# Uni-2_3.net
KiCad netlist of a schematic drawn in EAGLE
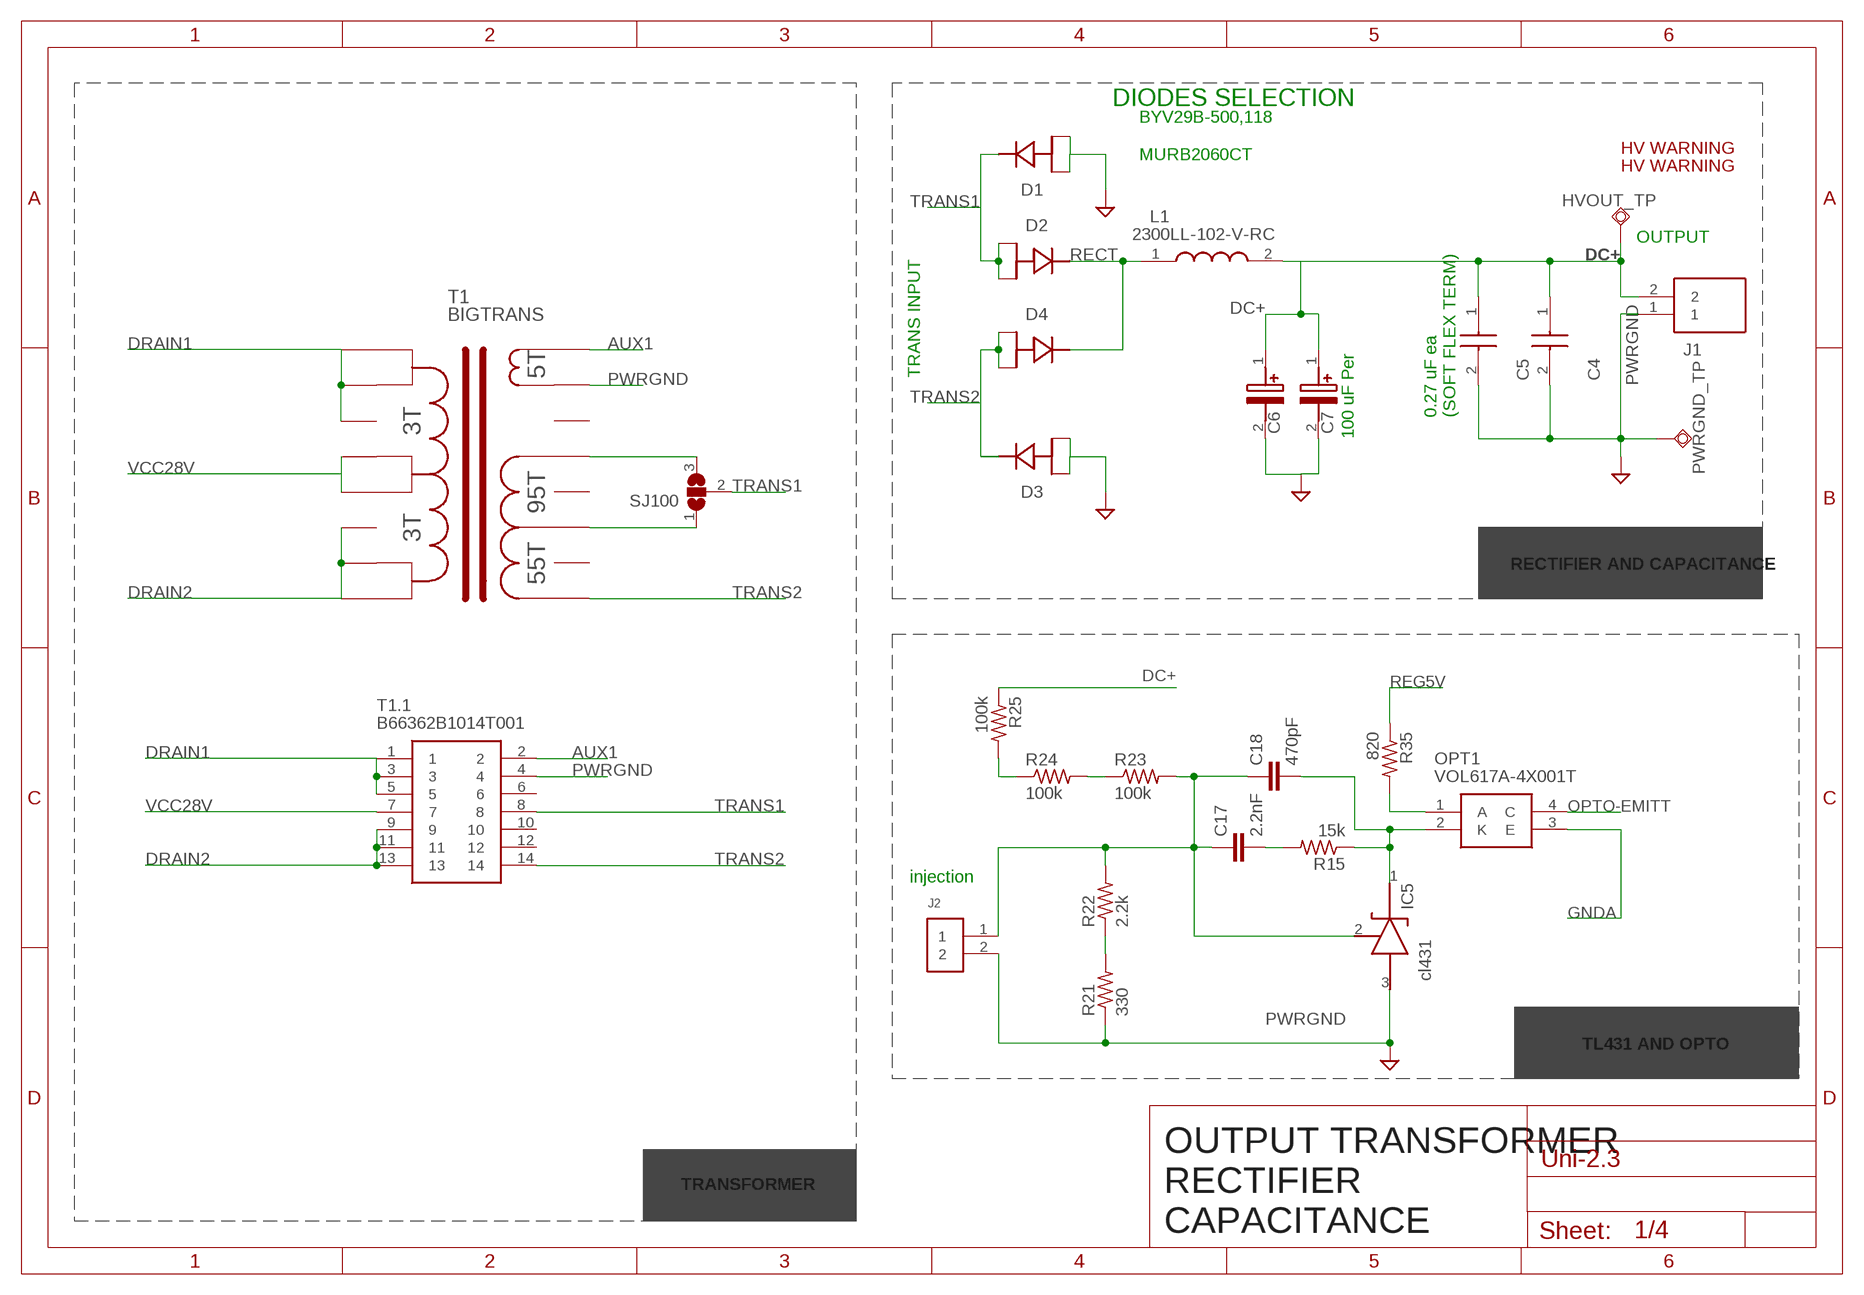
[diagram p0: schematic, sheet 1]
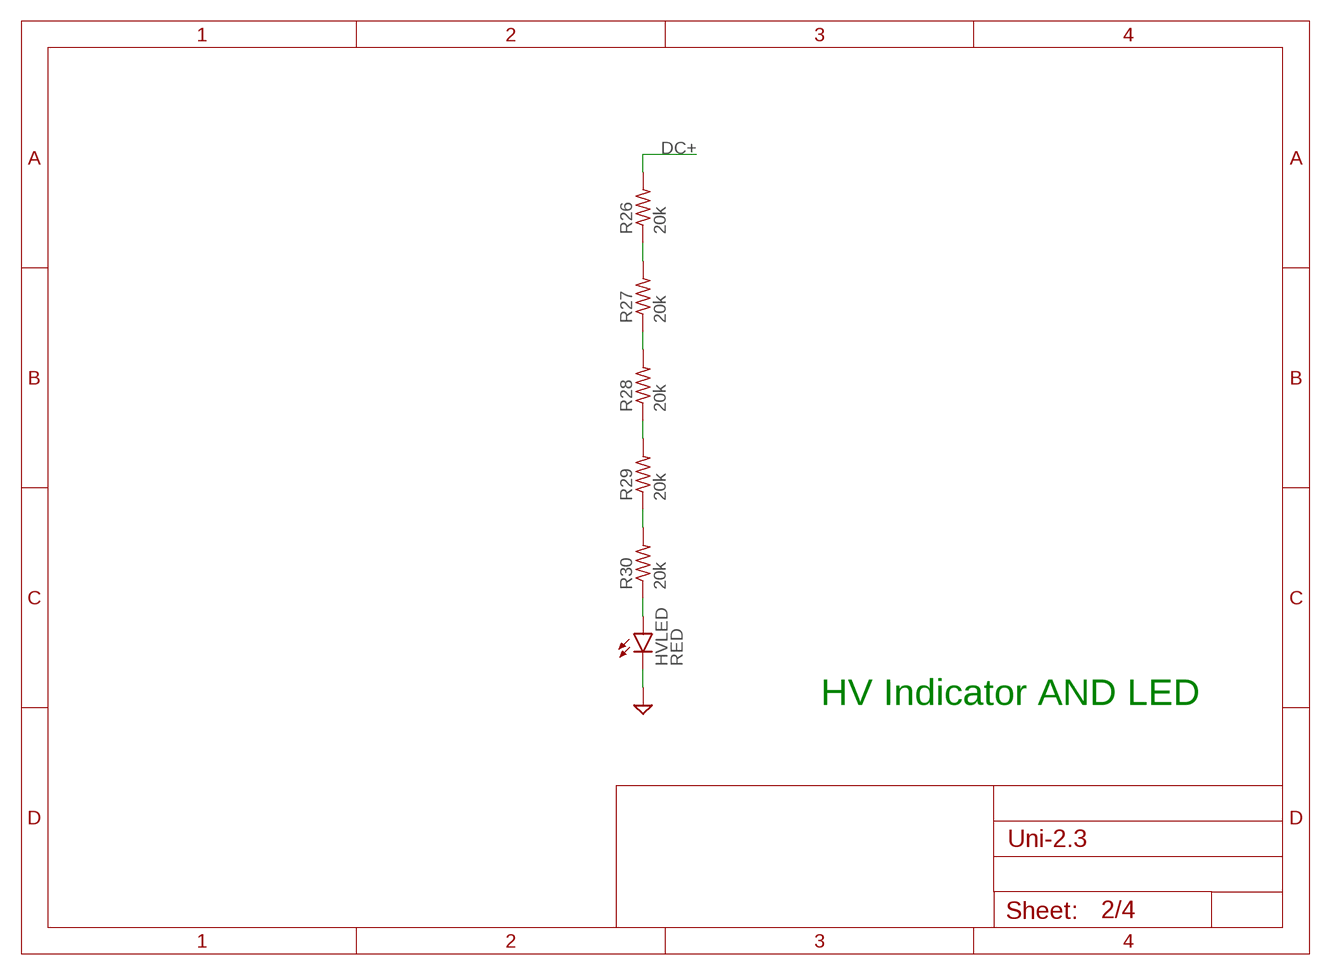
[diagram p1: schematic, sheet 2]
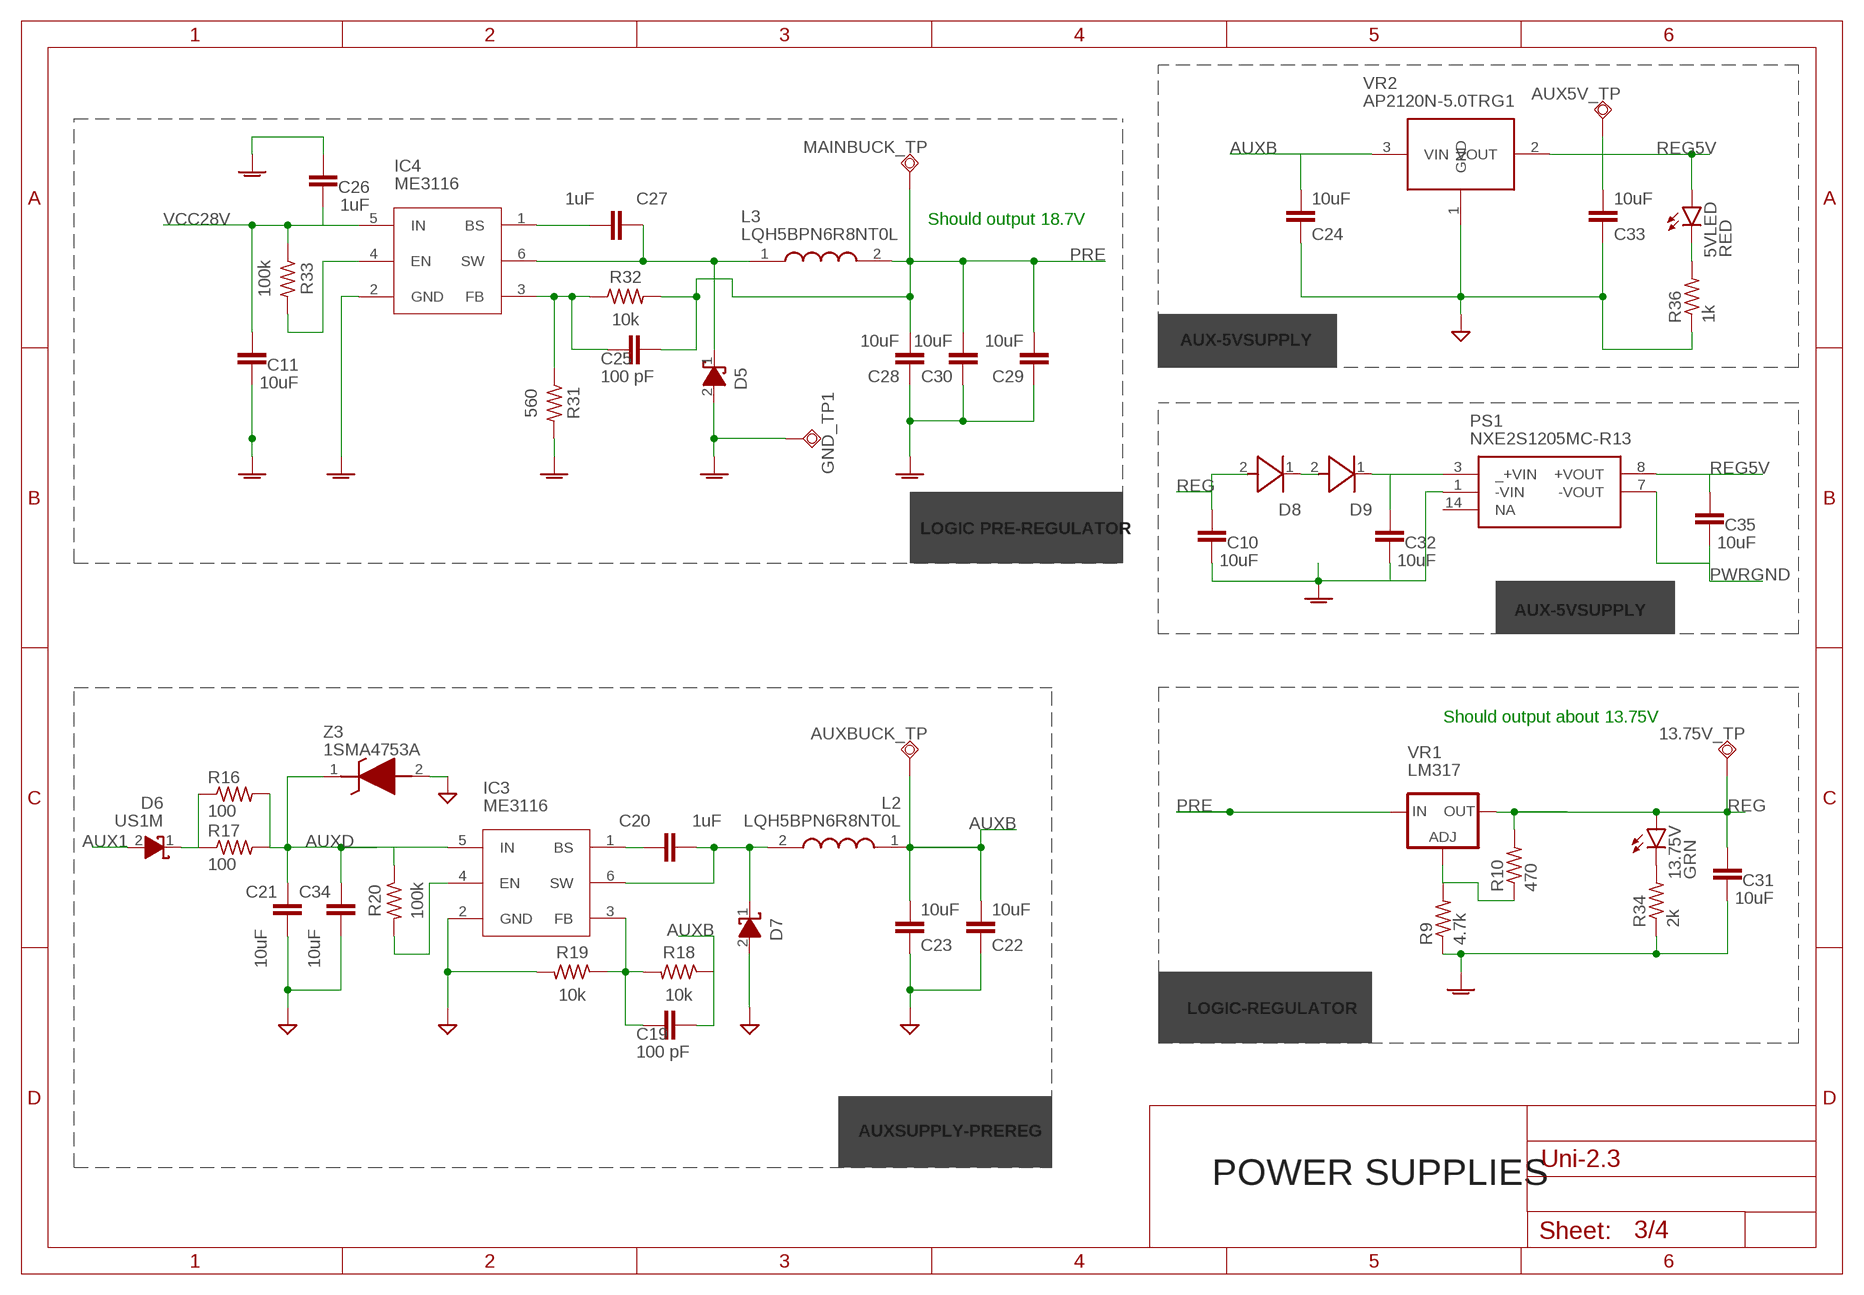
[diagram p2: schematic, sheet 3]
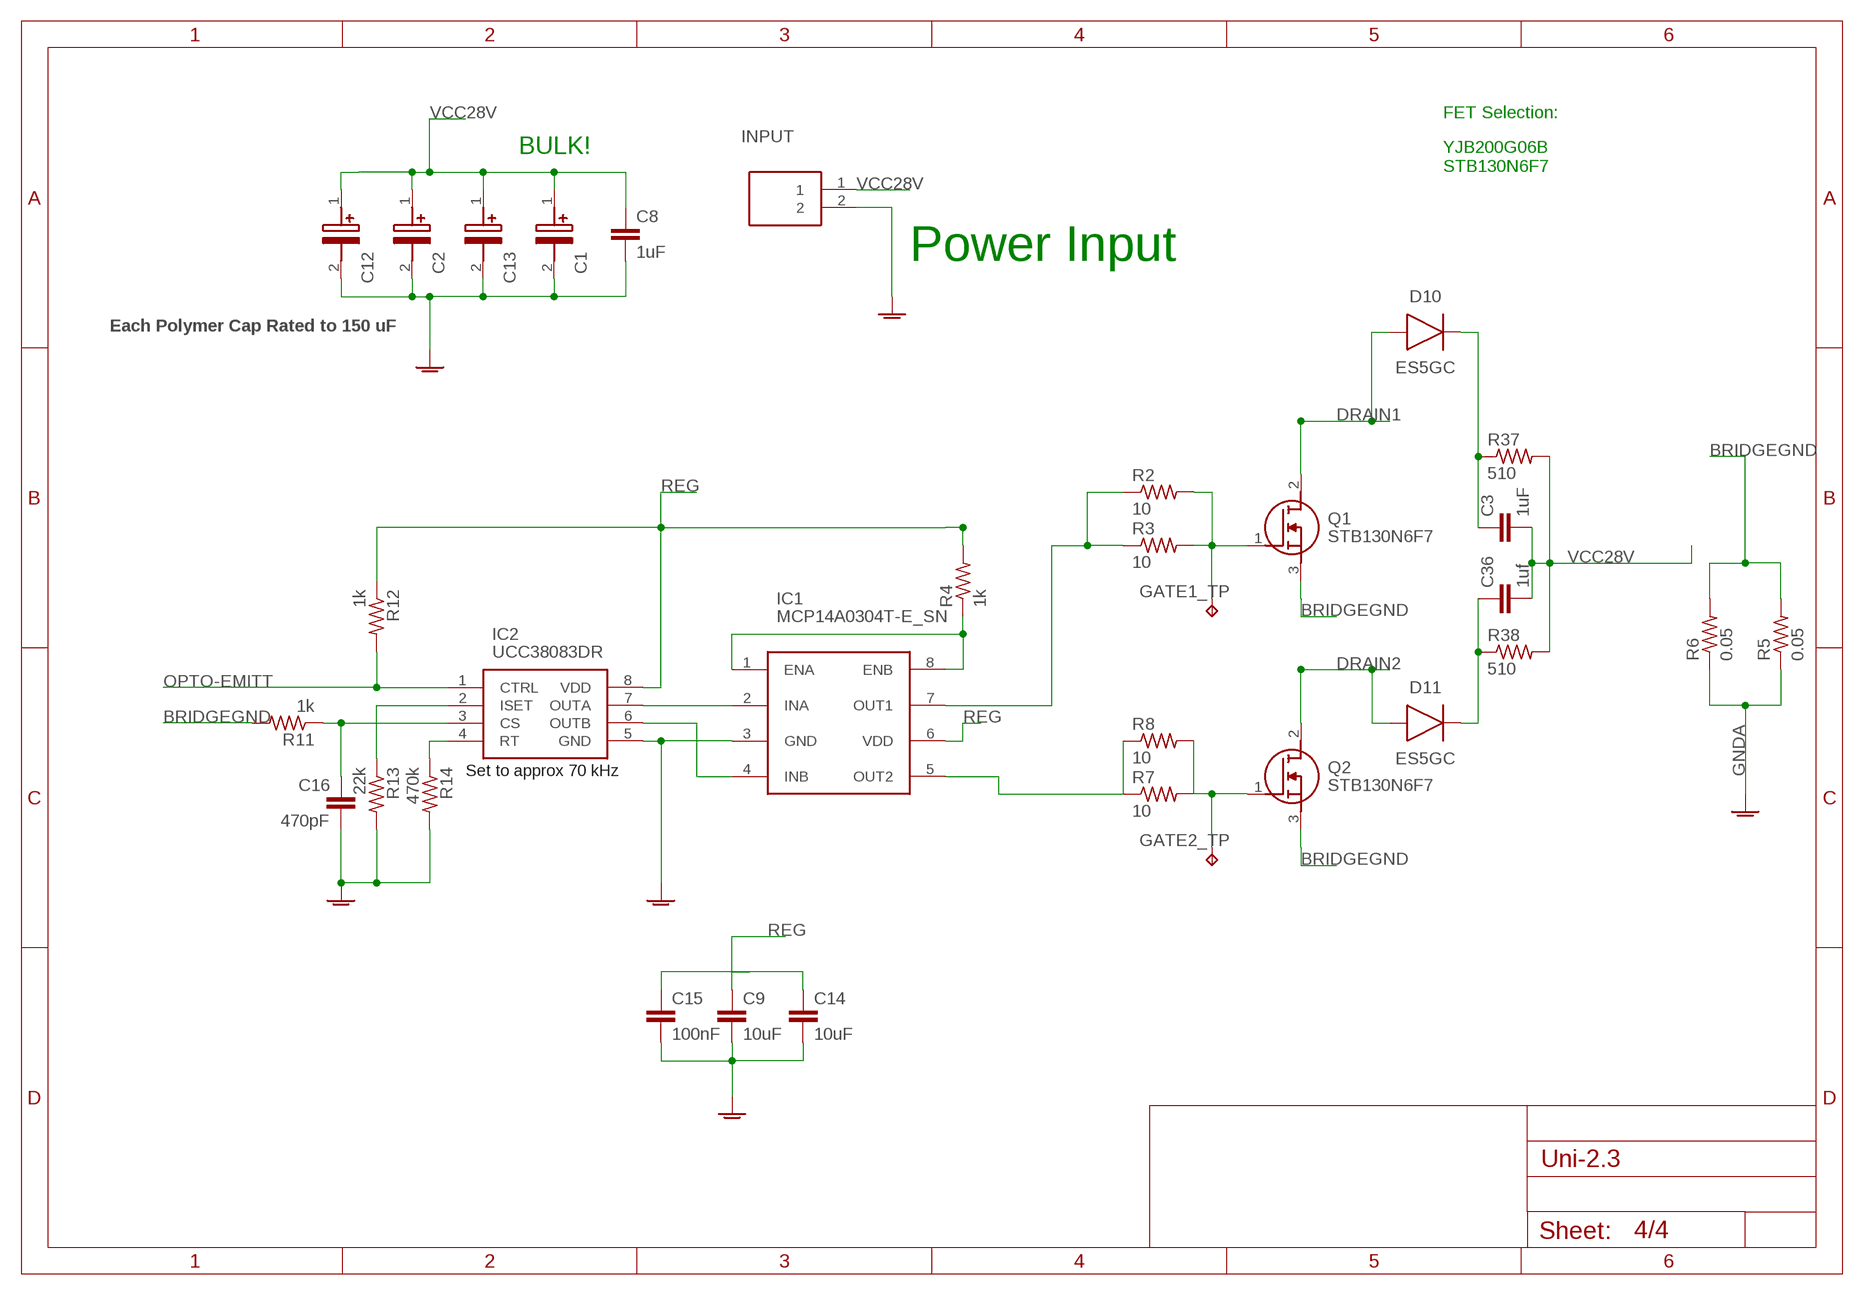
[diagram p3: schematic, sheet 4]

(export (version "E")
  (design (tool "Eeschema 10.0.6"))
  (components
    (comp (ref "HVLED")
      (value "RED")
      (footprint "eagle-import:CHIPLED_0805")
      (libsource (lib "eagle-import") (part "LEDCHIPLED_0805"))
    )
    (comp (ref "R26")
      (value "20k")
      (footprint "eagle-import:R1206")
      (libsource (lib "eagle-import") (part "R-US_R1206"))
    )
    (comp (ref "R27")
      (value "20k")
      (footprint "eagle-import:R1206")
      (libsource (lib "eagle-import") (part "R-US_R1206"))
    )
    (comp (ref "R28")
      (value "20k")
      (footprint "eagle-import:R1206")
      (libsource (lib "eagle-import") (part "R-US_R1206"))
    )
    (comp (ref "R29")
      (value "20k")
      (footprint "eagle-import:R1206")
      (libsource (lib "eagle-import") (part "R-US_R1206"))
    )
    (comp (ref "R30")
      (value "20k")
      (footprint "eagle-import:R1206")
      (libsource (lib "eagle-import") (part "R-US_R1206"))
    )
    (comp (ref "C1")
      (value "OVK151M1VTR-10131")
      (footprint "eagle-import:16SVF1000M")
      (libsource (lib "eagle-import") (part "OVK151M1VTR-10131"))
    )
    (comp (ref "C2")
      (value "OVK151M1VTR-10131")
      (footprint "eagle-import:16SVF1000M")
      (libsource (lib "eagle-import") (part "OVK151M1VTR-10131"))
    )
    (comp (ref "C3")
      (value "1uF")
      (footprint "eagle-import:C1206K")
      (libsource (lib "eagle-import") (part "rcl_334_C-EUC1206K"))
    )
    (comp (ref "C8")
      (value "1uF")
      (footprint "eagle-import:C0805K")
      (fields (field (name "LCSC_PART") "C440198"))
      (libsource (lib "eagle-import") (part "rcl_334_C-EUC0805K"))
    )
    (comp (ref "C9")
      (value "10uF")
      (footprint "eagle-import:C0603K")
      (fields (field (name "LCSC_PART") "C440198"))
      (libsource (lib "eagle-import") (part "rcl_334_C-EUC0603K"))
    )
    (comp (ref "C12")
      (value "OVK151M1VTR-10131")
      (footprint "eagle-import:16SVF1000M")
      (libsource (lib "eagle-import") (part "OVK151M1VTR-10131"))
    )
    (comp (ref "C13")
      (value "OVK151M1VTR-10131")
      (footprint "eagle-import:16SVF1000M")
      (libsource (lib "eagle-import") (part "OVK151M1VTR-10131"))
    )
    (comp (ref "C14")
      (value "10uF")
      (footprint "eagle-import:C0603K")
      (fields (field (name "LCSC_PART") "C440198"))
      (libsource (lib "eagle-import") (part "rcl_334_C-EUC0603K"))
    )
    (comp (ref "C15")
      (value "100nF")
      (footprint "eagle-import:C0603K")
      (fields (field (name "LCSC_PART") "C440198"))
      (libsource (lib "eagle-import") (part "rcl_334_C-EUC0603K"))
    )
    (comp (ref "C16")
      (value "470pF")
      (footprint "eagle-import:C0603K")
      (fields (field (name "LCSC_PART") "C1620"))
      (libsource (lib "eagle-import") (part "rcl_334_C-EUC0603K"))
    )
    (comp (ref "C36")
      (value "1uf")
      (footprint "eagle-import:C1206K")
      (libsource (lib "eagle-import") (part "rcl_334_C-EUC1206K"))
    )
    (comp (ref "D10")
      (value "ES5GC")
      (footprint "eagle-import:DIOM5226X290N")
      (fields (field (name "LCSC_PART") "C128705"))
      (libsource (lib "eagle-import") (part "DIODEDO-214AC(SMA)"))
    )
    (comp (ref "D11")
      (value "ES5GC")
      (footprint "eagle-import:DIOM5226X290N")
      (libsource (lib "eagle-import") (part "DIODEDO-214AC(SMA)"))
    )
    (comp (ref "GATE1_TP")
      (value "TPTP13R")
      (footprint "eagle-import:TP13R")
      (libsource (lib "eagle-import") (part "TPTP13R"))
    )
    (comp (ref "GATE2_TP")
      (value "TPTP13R")
      (footprint "eagle-import:TP13R")
      (libsource (lib "eagle-import") (part "TPTP13R"))
    )
    (comp (ref "IC1")
      (value "MCP14A0304T-E_SN")
      (footprint "eagle-import:SOIC127P600X175-8N")
      (fields
        (field (name "MANUFACTURER_PART_NUMBER") "MCP14A0304T-E/SN")
        (field (name "MOUSER_PART_NUMBER") "579-MCP14A0304T-E/SN")
      )
      (libsource (lib "eagle-import") (part "MCP14A0304T-E_SN"))
    )
    (comp (ref "IC2")
      (value "UCC38083DR")
      (footprint "eagle-import:SOIC127P600X175-8N")
      (fields (field (name "MOUSER_PART_NUMBER") "595-UCC38083DR"))
      (libsource (lib "eagle-import") (part "UCC38083DR"))
    )
    (comp (ref "INPUT")
      (value "TB005-762-02BE")
      (footprint "eagle-import:TB00576202BE")
      (fields (field (name "MOUSER_PART_NUMBER") "490-TB005-762-02BE"))
      (libsource (lib "eagle-import") (part "TB005-762-02BE"))
    )
    (comp (ref "Q1")
      (value "STB130N6F7")
      (footprint "eagle-import:D2PAK")
      (libsource (lib "eagle-import") (part "STB130N6F7"))
    )
    (comp (ref "Q2")
      (value "STB130N6F7")
      (footprint "eagle-import:D2PAK")
      (libsource (lib "eagle-import") (part "STB130N6F7"))
    )
    (comp (ref "R2")
      (value "10")
      (footprint "eagle-import:R0805")
      (libsource (lib "eagle-import") (part "R-US_R0805"))
    )
    (comp (ref "R3")
      (value "10")
      (footprint "eagle-import:R0805")
      (libsource (lib "eagle-import") (part "R-US_R0805"))
    )
    (comp (ref "R4")
      (value "1k")
      (footprint "eagle-import:R0402")
      (libsource (lib "eagle-import") (part "R-US_R0402"))
    )
    (comp (ref "R5")
      (value "0.05")
      (footprint "eagle-import:R2512")
      (libsource (lib "eagle-import") (part "R-US_R2512"))
    )
    (comp (ref "R6")
      (value "0.05")
      (footprint "eagle-import:R2512")
      (libsource (lib "eagle-import") (part "R-US_R2512"))
    )
    (comp (ref "R7")
      (value "10")
      (footprint "eagle-import:R0805")
      (libsource (lib "eagle-import") (part "R-US_R0805"))
    )
    (comp (ref "R8")
      (value "10")
      (footprint "eagle-import:R0805")
      (libsource (lib "eagle-import") (part "R-US_R0805"))
    )
    (comp (ref "R11")
      (value "1k")
      (footprint "eagle-import:R0603")
      (fields (field (name "LCSC_PART") "C21190"))
      (libsource (lib "eagle-import") (part "R-US_R0603"))
    )
    (comp (ref "R12")
      (value "1k")
      (footprint "eagle-import:R0603")
      (fields (field (name "LCSC_PART") "C22975"))
      (libsource (lib "eagle-import") (part "R-US_R0603"))
    )
    (comp (ref "R13")
      (value "22k")
      (footprint "eagle-import:R0603")
      (fields (field (name "LCSC_PART") "C31850"))
      (libsource (lib "eagle-import") (part "R-US_R0603"))
    )
    (comp (ref "R14")
      (value "470k")
      (footprint "eagle-import:R0603")
      (fields (field (name "LCSC_PART") "C25811"))
      (libsource (lib "eagle-import") (part "R-US_R0603"))
    )
    (comp (ref "R37")
      (value "510")
      (footprint "eagle-import:R2512")
      (libsource (lib "eagle-import") (part "R-US_R2512"))
    )
    (comp (ref "R38")
      (value "510")
      (footprint "eagle-import:R2512")
      (libsource (lib "eagle-import") (part "R-US_R2512"))
    )
    (comp (ref "5VLED")
      (value "RED")
      (footprint "eagle-import:CHIPLED_0805")
      (fields (field (name "LCSC_PART") "C72043"))
      (libsource (lib "eagle-import") (part "LEDCHIPLED_0805"))
    )
    (comp (ref "13.75V")
      (value "GRN")
      (footprint "eagle-import:CHIPLED_0805")
      (fields (field (name "LCSC_PART") "C72043"))
      (libsource (lib "eagle-import") (part "LEDCHIPLED_0805"))
    )
    (comp (ref "13.75V_TP")
      (value "TPSQPAD1-17")
      (footprint "eagle-import:P1-17")
      (libsource (lib "eagle-import") (part "TPSQPAD1-17"))
    )
    (comp (ref "AUX5V_TP")
      (value "TPSQPAD1-17")
      (footprint "eagle-import:P1-17")
      (libsource (lib "eagle-import") (part "TPSQPAD1-17"))
    )
    (comp (ref "AUXBUCK_TP")
      (value "TPSQPAD1-17")
      (footprint "eagle-import:P1-17")
      (libsource (lib "eagle-import") (part "TPSQPAD1-17"))
    )
    (comp (ref "C10")
      (value "10uF")
      (footprint "eagle-import:C0805K")
      (fields (field (name "LCSC_PART") "C440198"))
      (libsource (lib "eagle-import") (part "C-EUC0805K"))
    )
    (comp (ref "C11")
      (value "10uF")
      (footprint "eagle-import:C0805K")
      (fields (field (name "LCSC_PART") "C440198"))
      (libsource (lib "eagle-import") (part "C-EUC0805K"))
    )
    (comp (ref "C19")
      (value "100 pF")
      (footprint "eagle-import:C0402K")
      (fields (field (name "LCSC_PART") "C1546"))
      (libsource (lib "eagle-import") (part "rcl_334_C-EUC0402K"))
    )
    (comp (ref "C20")
      (value "1uF")
      (footprint "eagle-import:C0603K")
      (fields (field (name "LCSC_PART") "C14663"))
      (libsource (lib "eagle-import") (part "rcl_334_C-EUC0603K"))
    )
    (comp (ref "C21")
      (value "10uF")
      (footprint "eagle-import:C0805K")
      (libsource (lib "eagle-import") (part "rcl_334_C-EUC0805K"))
    )
    (comp (ref "C22")
      (value "10uF")
      (footprint "eagle-import:C0402")
      (fields (field (name "LCSC_PART") "C440198"))
      (libsource (lib "eagle-import") (part "rcl_334_C-EUC0402"))
    )
    (comp (ref "C23")
      (value "10uF")
      (footprint "eagle-import:C0603K")
      (fields (field (name "LCSC_PART") "C440198"))
      (libsource (lib "eagle-import") (part "rcl_334_C-EUC0603K"))
    )
    (comp (ref "C24")
      (value "10uF")
      (footprint "eagle-import:C0603K")
      (fields (field (name "LCSC_PART") "C440198"))
      (libsource (lib "eagle-import") (part "rcl_334_C-EUC0603K"))
    )
    (comp (ref "C25")
      (value "100 pF")
      (footprint "eagle-import:C0402K")
      (fields (field (name "LCSC_PART") "C1546"))
      (libsource (lib "eagle-import") (part "rcl_334_C-EUC0402K"))
    )
    (comp (ref "C26")
      (value "1uF")
      (footprint "eagle-import:C0603K")
      (fields (field (name "LCSC_PART") "C440198"))
      (libsource (lib "eagle-import") (part "rcl_334_C-EUC0603K"))
    )
    (comp (ref "C27")
      (value "1uF")
      (footprint "eagle-import:C0603K")
      (fields (field (name "LCSC_PART") "C14663"))
      (libsource (lib "eagle-import") (part "rcl_334_C-EUC0603K"))
    )
    (comp (ref "C28")
      (value "10uF")
      (footprint "eagle-import:C0805K")
      (fields (field (name "LCSC_PART") "C440198"))
      (libsource (lib "eagle-import") (part "C-EUC0805K"))
    )
    (comp (ref "C29")
      (value "10uF")
      (footprint "eagle-import:C0805K")
      (fields (field (name "LCSC_PART") "C440198"))
      (libsource (lib "eagle-import") (part "C-EUC0805K"))
    )
    (comp (ref "C30")
      (value "10uF")
      (footprint "eagle-import:C0805K")
      (fields (field (name "LCSC_PART") "C440198"))
      (libsource (lib "eagle-import") (part "C-EUC0805K"))
    )
    (comp (ref "C31")
      (value "10uF")
      (footprint "eagle-import:C0805K")
      (fields (field (name "LCSC_PART") "C440198"))
      (libsource (lib "eagle-import") (part "C-EUC0805K"))
    )
    (comp (ref "C32")
      (value "10uF")
      (footprint "eagle-import:C0603K")
      (fields (field (name "LCSC_PART") "C440198"))
      (libsource (lib "eagle-import") (part "rcl_334_C-EUC0603K"))
    )
    (comp (ref "C33")
      (value "10uF")
      (footprint "eagle-import:C0603K")
      (libsource (lib "eagle-import") (part "rcl_334_C-EUC0603K"))
    )
    (comp (ref "C34")
      (value "10uF")
      (footprint "eagle-import:C0805K")
      (libsource (lib "eagle-import") (part "rcl_334_C-EUC0805K"))
    )
    (comp (ref "C35")
      (value "10uF")
      (footprint "eagle-import:C0603K")
      (fields (field (name "LCSC_PART") "C440198"))
      (libsource (lib "eagle-import") (part "rcl_334_C-EUC0603K"))
    )
    (comp (ref "D5")
      (value "SCHOTTKY")
      (footprint "eagle-import:DIOM5127X229N")
      (fields
        (field (name "MANUFACTURER_PART_NUMBER") "SS16HE3_B/H")
        (field (name "MOUSER_PART_NUMBER") "78-SS16HE3_B/H")
        (field (name "LCSC_PART") "C22452")
      )
      (libsource (lib "eagle-import") (part "SCHOTTKY"))
    )
    (comp (ref "D6")
      (value "US1M")
      (footprint "eagle-import:DIOM5127X229N")
      (fields
        (field (name "MANUFACTURER_PART_NUMBER") "SS16HE3_B/H")
        (field (name "MOUSER_PART_NUMBER") "78-SS16HE3_B/H")
      )
      (libsource (lib "eagle-import") (part "SCHOTTKY"))
    )
    (comp (ref "D7")
      (value "SCHOTTKY")
      (footprint "eagle-import:DIOM5127X229N")
      (fields
        (field (name "MANUFACTURER_PART_NUMBER") "SS16HE3_B/H")
        (field (name "MOUSER_PART_NUMBER") "78-SS16HE3_B/H")
        (field (name "LCSC_PART") "C22452")
      )
      (libsource (lib "eagle-import") (part "SCHOTTKY"))
    )
    (comp (ref "D8")
      (value "SM4007PL")
      (footprint "eagle-import:SOD3716X145N")
      (fields
        (field (name "MANUFACTURER_PART_NUMBER") "1N4148W-7-F")
        (field (name "MOUSER_PART_NUMBER") "621-1N4148W-F")
        (field (name "LCSC_PART") "C64898")
      )
      (libsource (lib "eagle-import") (part "1N4148W-7-F"))
    )
    (comp (ref "D9")
      (value "SM4007PL")
      (footprint "eagle-import:SOD3716X145N")
      (fields
        (field (name "MANUFACTURER_PART_NUMBER") "1N4148W-7-F")
        (field (name "MOUSER_PART_NUMBER") "621-1N4148W-F")
        (field (name "LCSC_PART") "C64898")
      )
      (libsource (lib "eagle-import") (part "1N4148W-7-F"))
    )
    (comp (ref "GND_TP1")
      (value "TPSQPAD1-13")
      (footprint "eagle-import:P1-13")
      (libsource (lib "eagle-import") (part "TPSQPAD1-13"))
    )
    (comp (ref "IC3")
      (value "ME3116")
      (footprint "eagle-import:SOT95P280X100-6N")
      (fields (field (name "LCSC_PART") "C97643"))
      (libsource (lib "eagle-import") (part "ME3116"))
    )
    (comp (ref "IC4")
      (value "ME3116")
      (footprint "eagle-import:SOT95P280X100-6N")
      (fields (field (name "LCSC_PART") "C97643"))
      (libsource (lib "eagle-import") (part "ME3116"))
    )
    (comp (ref "L2")
      (value "LQH5BPN6R8NT0L")
      (footprint "eagle-import:LQH5BPB100MT0L")
      (fields (field (name "MOUSER_PART_NUMBER") "81-LQH5BPN6R8NT0L0L"))
      (libsource (lib "eagle-import") (part "LQH5BPN6R8NT0L"))
    )
    (comp (ref "L3")
      (value "LQH5BPN6R8NT0L")
      (footprint "eagle-import:LQH5BPB100MT0L")
      (fields (field (name "MOUSER_PART_NUMBER") "81-LQH5BPN6R8NT0L0L"))
      (libsource (lib "eagle-import") (part "LQH5BPN6R8NT0L"))
    )
    (comp (ref "MAINBUCK_TP")
      (value "TPSQPAD1-17")
      (footprint "eagle-import:P1-17")
      (libsource (lib "eagle-import") (part "TPSQPAD1-17"))
    )
    (comp (ref "PS1")
      (value "NXE2S1205MC-R13")
      (footprint "eagle-import:NXE2S1205MCR13")
      (fields (field (name "MOUSER_PART_NUMBER") "580-NXE2S1205MC-R13"))
      (libsource (lib "eagle-import") (part "NXE2S1205MC-R13"))
    )
    (comp (ref "R9")
      (value "4.7k")
      (footprint "eagle-import:R0603")
      (fields (field (name "LCSC_PART") "C22975"))
      (libsource (lib "eagle-import") (part "R-US_R0603"))
    )
    (comp (ref "R10")
      (value "470")
      (footprint "eagle-import:R0603")
      (fields (field (name "LCSC_PART") "C22975"))
      (libsource (lib "eagle-import") (part "R-US_R0603"))
    )
    (comp (ref "R16")
      (value "100")
      (footprint "eagle-import:R1206")
      (libsource (lib "eagle-import") (part "R-US_R1206"))
    )
    (comp (ref "R17")
      (value "100")
      (footprint "eagle-import:R1206")
      (libsource (lib "eagle-import") (part "R-US_R1206"))
    )
    (comp (ref "R18")
      (value "10k")
      (footprint "eagle-import:R0402")
      (fields (field (name "LCSC_PART") "C25779"))
      (libsource (lib "eagle-import") (part "R-US_R0402"))
    )
    (comp (ref "R19")
      (value "10k")
      (footprint "eagle-import:R0402")
      (fields (field (name "LCSC_PART") "C25779"))
      (libsource (lib "eagle-import") (part "R-US_R0402"))
    )
    (comp (ref "R20")
      (value "100k")
      (footprint "eagle-import:R0402")
      (fields (field (name "LCSC_PART") "C25741") (field (name "SPICEPREFIX") "R"))
      (libsource (lib "eagle-import") (part "R-US_R0402"))
    )
    (comp (ref "R31")
      (value "560")
      (footprint "eagle-import:R0402")
      (fields (field (name "LCSC_PART") "C4177") (field (name "SPICEPREFIX") "R"))
      (libsource (lib "eagle-import") (part "R-US_R0402"))
    )
    (comp (ref "R32")
      (value "10k")
      (footprint "eagle-import:R0402")
      (fields (field (name "LCSC_PART") "C25779"))
      (libsource (lib "eagle-import") (part "R-US_R0402"))
    )
    (comp (ref "R33")
      (value "100k")
      (footprint "eagle-import:R0402")
      (fields (field (name "LCSC_PART") "C25741") (field (name "SPICEPREFIX") "R"))
      (libsource (lib "eagle-import") (part "R-US_R0402"))
    )
    (comp (ref "R34")
      (value "2k")
      (footprint "eagle-import:R0603")
      (fields (field (name "LCSC_PART") "C22975"))
      (libsource (lib "eagle-import") (part "R-US_R0603"))
    )
    (comp (ref "R36")
      (value "1k")
      (footprint "eagle-import:R0603")
      (fields (field (name "LCSC_PART") "C22975"))
      (libsource (lib "eagle-import") (part "R-US_R0603"))
    )
    (comp (ref "VR1")
      (value "LM317")
      (footprint "eagle-import:DPACK")
      (libsource (lib "eagle-import") (part "LM317?MBDT"))
    )
    (comp (ref "VR2")
      (value "AP2120N-5.0TRG1")
      (footprint "eagle-import:SOT95P240X120-3N")
      (fields (field (name "MOUSER_PART_NUMBER") "621-AP2120N-5.0TRG1"))
      (libsource (lib "eagle-import") (part "AP2120N-5.0TRG1"))
    )
    (comp (ref "Z3")
      (value "1SMA4753A")
      (footprint "eagle-import:DIOM5226X220N")
      (fields
        (field (name "MANUFACTURER_PART_NUMBER") "1SMA5942BT3G")
        (field (name "MOUSER_PART_NUMBER") "863-1SMA5942BT3G")
        (field (name "LCSC_PART") "C362284")
      )
      (libsource (lib "eagle-import") (part "1SMA5942BT3G"))
    )
    (comp (ref "C4")
      (value "C1812C274KCRACAUTO")
      (footprint "eagle-import:C1812")
      (fields (field (name "MOUSER_PART_NUMBER") "80-C1812C274KCRAUTO"))
      (libsource (lib "eagle-import") (part "C1812C274KCRACAUTO"))
    )
    (comp (ref "C5")
      (value "C1812C274KCRACAUTO")
      (footprint "eagle-import:C1812")
      (fields (field (name "MOUSER_PART_NUMBER") "80-C1812C274KCRAUTO"))
      (libsource (lib "eagle-import") (part "C1812C274KCRACAUTO"))
    )
    (comp (ref "C6")
      (value "400BXW100MEFR18X25")
      (footprint "eagle-import:CAPPRD750W80D1825H2700")
      (libsource (lib "eagle-import") (part "400BXW100MEFR18X25"))
    )
    (comp (ref "C7")
      (value "400BXW100MEFR18X25")
      (footprint "eagle-import:CAPPRD750W80D1825H2700")
      (libsource (lib "eagle-import") (part "400BXW100MEFR18X25"))
    )
    (comp (ref "C17")
      (value "2.2nF")
      (footprint "eagle-import:C0603K")
      (libsource (lib "eagle-import") (part "rcl_334_C-EUC0603K"))
    )
    (comp (ref "C18")
      (value "470pF")
      (footprint "eagle-import:C0603K")
      (libsource (lib "eagle-import") (part "rcl_334_C-EUC0603K"))
    )
    (comp (ref "D1")
      (value "FERD20H60CG-TR")
      (footprint "eagle-import:STB20N95K5")
      (fields (field (name "MOUSER_PART_NUMBER") "511-FERD20H60CG-TR"))
      (libsource (lib "eagle-import") (part "FERD20H60CG-TR"))
    )
    (comp (ref "D2")
      (value "FERD20H60CG-TR")
      (footprint "eagle-import:STB20N95K5")
      (fields (field (name "MOUSER_PART_NUMBER") "511-FERD20H60CG-TR"))
      (libsource (lib "eagle-import") (part "FERD20H60CG-TR"))
    )
    (comp (ref "D3")
      (value "FERD20H60CG-TR")
      (footprint "eagle-import:STB20N95K5")
      (fields (field (name "MOUSER_PART_NUMBER") "511-FERD20H60CG-TR"))
      (libsource (lib "eagle-import") (part "FERD20H60CG-TR"))
    )
    (comp (ref "D4")
      (value "FERD20H60CG-TR")
      (footprint "eagle-import:STB20N95K5")
      (fields (field (name "MOUSER_PART_NUMBER") "511-FERD20H60CG-TR"))
      (libsource (lib "eagle-import") (part "FERD20H60CG-TR"))
    )
    (comp (ref "HVOUT_TP")
      (value "TPSQPAD1-13")
      (footprint "eagle-import:P1-13")
      (libsource (lib "eagle-import") (part "TPSQPAD1-13"))
    )
    (comp (ref "IC5")
      (value "cl431")
      (footprint "eagle-import:SOT95P237X112-3N")
      (fields
        (field (name "MANUFACTURER_PART_NUMBER") "TL431CL3T")
        (field (name "MOUSER_PART_NUMBER") "511-TL431CL3T")
      )
      (libsource (lib "eagle-import") (part "TL431CL3T"))
    )
    (comp (ref "J1")
      (value "TB005-762-02BE")
      (footprint "eagle-import:TB00576202BE")
      (fields (field (name "MOUSER_PART_NUMBER") "490-TB005-762-02BE"))
      (libsource (lib "eagle-import") (part "TB005-762-02BE"))
    )
    (comp (ref "J2")
      (value "61300211121")
      (footprint "eagle-import:61300211121")
      (fields
        (field (name "DIGI_KEY_PART_NUMBER") "732-5315-ND")
        (field (name "MANUFACTURER") "Wurth Electronics Inc.")
        (field (name "CREATED_BY") "PCBLayout.com")
      )
      (libsource (lib "eagle-import") (part "61300211121"))
    )
    (comp (ref "L1")
      (value "2300LL-102-V-RC")
      (footprint "eagle-import:2300LL102VRC")
      (fields (field (name "MOUSER_PART_NUMBER") "652-2300LL-102-V-RC"))
      (libsource (lib "eagle-import") (part "2300LL-102-V-RC"))
    )
    (comp (ref "OPT1")
      (value "VOL617A-4X001T")
      (footprint "eagle-import:SOP254P1015X230-4N")
      (fields (field (name "MOUSER_PART_NUMBER") "78-VOL617A-4X001T"))
      (libsource (lib "eagle-import") (part "VOL617A-4X001T"))
    )
    (comp (ref "PWRGND_TP")
      (value "TPSQPAD1-13")
      (footprint "eagle-import:P1-13")
      (libsource (lib "eagle-import") (part "TPSQPAD1-13"))
    )
    (comp (ref "R15")
      (value "15k")
      (footprint "eagle-import:R0603")
      (libsource (lib "eagle-import") (part "R-US_R0603"))
    )
    (comp (ref "R21")
      (value "330")
      (footprint "eagle-import:R0805")
      (libsource (lib "eagle-import") (part "R-US_R0805"))
    )
    (comp (ref "R22")
      (value "2.2k")
      (footprint "eagle-import:R0805")
      (libsource (lib "eagle-import") (part "R-US_R0805"))
    )
    (comp (ref "R23")
      (value "100k")
      (footprint "eagle-import:R1206")
      (libsource (lib "eagle-import") (part "R-US_R1206"))
    )
    (comp (ref "R24")
      (value "100k")
      (footprint "eagle-import:R1206")
      (libsource (lib "eagle-import") (part "R-US_R1206"))
    )
    (comp (ref "R25")
      (value "100k")
      (footprint "eagle-import:R1206")
      (libsource (lib "eagle-import") (part "R-US_R1206"))
    )
    (comp (ref "R35")
      (value "820")
      (footprint "eagle-import:R0603")
      (libsource (lib "eagle-import") (part "R-US_R0603"))
    )
    (comp (ref "SJ100")
      (value "SJ2WW")
      (footprint "eagle-import:SJ_2W")
      (libsource (lib "eagle-import") (part "SJ2WW"))
    )
    (comp (ref "T1")
      (value "BIGTRANS")
      (footprint "eagle-import:BIGTRANS!")
      (libsource (lib "eagle-import") (part "BIGTRANS"))
    )
    (comp (ref "T1.1")
      (value "B66362B1014T001")
      (footprint "eagle-import:B66362B1014T001")
      (fields (field (name "MOUSER_PART_NUMBER") "871-B66362B1014T001"))
      (libsource (lib "eagle-import") (part "B66362B1014T001"))
    )
    (comp (ref "U$3")
      (value "HV")
      (footprint "eagle-import:PSFBC_ELECTRIC_SHOCK")
      (libsource (lib "eagle-import") (part "HV"))
    )
    (comp (ref "U$4")
      (value "HV")
      (footprint "eagle-import:PSFBC_ELECTRIC_SHOCK")
      (libsource (lib "eagle-import") (part "HV"))
    )
  )
  (nets
    (net (code "1") (name "AUX1") (class "Default")
      (node (ref "D6") (pin "2") (pinfunction "A_2") (pintype "bidirectional"))
      (node (ref "T1") (pin "16") (pinfunction "16_16") (pintype "bidirectional"))
      (node (ref "T1.1") (pin "2") (pinfunction "2_2") (pintype "bidirectional"))
    )
    (net (code "2") (name "AUXB") (class "Default")
      (node (ref "AUXBUCK_TP") (pin "TP") (pinfunction "TP_TP") (pintype "input"))
      (node (ref "C19") (pin "1") (pinfunction "1_1") (pintype "passive"))
      (node (ref "C22") (pin "2") (pinfunction "2_2") (pintype "passive"))
      (node (ref "C23") (pin "2") (pinfunction "2_2") (pintype "passive"))
      (node (ref "C24") (pin "2") (pinfunction "2_2") (pintype "passive"))
      (node (ref "L2") (pin "1") (pinfunction "1_1") (pintype "bidirectional"))
      (node (ref "R18") (pin "1") (pinfunction "1_1") (pintype "passive"))
      (node (ref "VR2") (pin "3") (pinfunction "VIN_3") (pintype "bidirectional"))
    )
    (net (code "3") (name "AUXD") (class "Default")
      (node (ref "C21") (pin "1") (pinfunction "1_1") (pintype "passive"))
      (node (ref "C34") (pin "1") (pinfunction "1_1") (pintype "passive"))
      (node (ref "IC3") (pin "5") (pinfunction "IN_5") (pintype "bidirectional"))
      (node (ref "R16") (pin "2") (pinfunction "2_2") (pintype "passive"))
      (node (ref "R17") (pin "2") (pinfunction "2_2") (pintype "passive"))
      (node (ref "R20") (pin "1") (pinfunction "1_1") (pintype "passive"))
      (node (ref "Z3") (pin "1") (pinfunction "K_1") (pintype "bidirectional"))
    )
    (net (code "4") (name "BRIDGEGND") (class "Default")
      (node (ref "Q1") (pin "3") (pinfunction "S_3") (pintype "bidirectional"))
      (node (ref "Q2") (pin "3") (pinfunction "S_3") (pintype "bidirectional"))
      (node (ref "R11") (pin "2") (pinfunction "2_2") (pintype "passive"))
      (node (ref "R5") (pin "2") (pinfunction "2_2") (pintype "passive"))
      (node (ref "R6") (pin "2") (pinfunction "2_2") (pintype "passive"))
    )
    (net (code "5") (name "DC+") (class "Default")
      (node (ref "C4") (pin "1") (pinfunction "1_1") (pintype "bidirectional"))
      (node (ref "C5") (pin "1") (pinfunction "1_1") (pintype "bidirectional"))
      (node (ref "C6") (pin "1") (pinfunction "+_1") (pintype "bidirectional"))
      (node (ref "C7") (pin "1") (pinfunction "+_1") (pintype "bidirectional"))
      (node (ref "HVOUT_TP") (pin "TP") (pinfunction "TP_TP") (pintype "input"))
      (node (ref "J1") (pin "2") (pinfunction "2_2") (pintype "bidirectional"))
      (node (ref "L1") (pin "2") (pinfunction "2_2") (pintype "bidirectional"))
      (node (ref "R25") (pin "1") (pinfunction "1_1") (pintype "passive"))
      (node (ref "R26") (pin "2") (pinfunction "2_2") (pintype "passive"))
    )
    (net (code "6") (name "DRAIN1") (class "Default")
      (node (ref "D10") (pin "2") (pinfunction "A_2") (pintype "passive"))
      (node (ref "Q1") (pin "2") (pinfunction "D_2") (pintype "bidirectional"))
      (node (ref "T1") (pin "6") (pinfunction "6_6") (pintype "bidirectional"))
      (node (ref "T1") (pin "7") (pinfunction "7_7") (pintype "bidirectional"))
      (node (ref "T1") (pin "8") (pinfunction "8_8") (pintype "bidirectional"))
      (node (ref "T1.1") (pin "1") (pinfunction "1_1") (pintype "bidirectional"))
      (node (ref "T1.1") (pin "3") (pinfunction "3_3") (pintype "bidirectional"))
      (node (ref "T1.1") (pin "5") (pinfunction "5_5") (pintype "bidirectional"))
    )
    (net (code "7") (name "DRAIN2") (class "Default")
      (node (ref "D11") (pin "2") (pinfunction "A_2") (pintype "passive"))
      (node (ref "Q2") (pin "2") (pinfunction "D_2") (pintype "bidirectional"))
      (node (ref "T1") (pin "1") (pinfunction "1_1") (pintype "bidirectional"))
      (node (ref "T1") (pin "2") (pinfunction "2_2") (pintype "bidirectional"))
      (node (ref "T1") (pin "3") (pinfunction "3_3") (pintype "bidirectional"))
      (node (ref "T1.1") (pin "11") (pinfunction "11_11") (pintype "bidirectional"))
      (node (ref "T1.1") (pin "13") (pinfunction "13_13") (pintype "bidirectional"))
      (node (ref "T1.1") (pin "9") (pinfunction "9_9") (pintype "bidirectional"))
    )
    (net (code "8") (name "GNDA") (class "Default")
      (node (ref "C1") (pin "2") (pinfunction "-_2") (pintype "bidirectional"))
      (node (ref "C10") (pin "1") (pinfunction "1_1") (pintype "passive"))
      (node (ref "C11") (pin "1") (pinfunction "1_1") (pintype "passive"))
      (node (ref "C12") (pin "2") (pinfunction "-_2") (pintype "bidirectional"))
      (node (ref "C13") (pin "2") (pinfunction "-_2") (pintype "bidirectional"))
      (node (ref "C14") (pin "2") (pinfunction "2_2") (pintype "passive"))
      (node (ref "C15") (pin "2") (pinfunction "2_2") (pintype "passive"))
      (node (ref "C16") (pin "2") (pinfunction "2_2") (pintype "passive"))
      (node (ref "C2") (pin "2") (pinfunction "-_2") (pintype "bidirectional"))
      (node (ref "C26") (pin "2") (pinfunction "2_2") (pintype "passive"))
      (node (ref "C28") (pin "1") (pinfunction "1_1") (pintype "passive"))
      (node (ref "C29") (pin "1") (pinfunction "1_1") (pintype "passive"))
      (node (ref "C30") (pin "1") (pinfunction "1_1") (pintype "passive"))
      (node (ref "C31") (pin "1") (pinfunction "1_1") (pintype "passive"))
      (node (ref "C32") (pin "1") (pinfunction "1_1") (pintype "passive"))
      (node (ref "C8") (pin "2") (pinfunction "2_2") (pintype "passive"))
      (node (ref "C9") (pin "2") (pinfunction "2_2") (pintype "passive"))
      (node (ref "D5") (pin "2") (pinfunction "A_2") (pintype "bidirectional"))
      (node (ref "GND_TP1") (pin "TP") (pinfunction "TP_TP") (pintype "input"))
      (node (ref "IC1") (pin "3") (pinfunction "GND_3") (pintype "bidirectional"))
      (node (ref "IC2") (pin "5") (pinfunction "GND_5") (pintype "bidirectional"))
      (node (ref "IC4") (pin "2") (pinfunction "GND_2") (pintype "bidirectional"))
      (node (ref "INPUT") (pin "2") (pinfunction "2_2") (pintype "bidirectional"))
      (node (ref "OPT1") (pin "3") (pinfunction "E_3") (pintype "bidirectional"))
      (node (ref "PS1") (pin "1") (pinfunction "-VIN_1") (pintype "bidirectional"))
      (node (ref "R13") (pin "2") (pinfunction "2_2") (pintype "passive"))
      (node (ref "R14") (pin "2") (pinfunction "2_2") (pintype "passive"))
      (node (ref "R31") (pin "2") (pinfunction "2_2") (pintype "passive"))
      (node (ref "R34") (pin "1") (pinfunction "1_1") (pintype "passive"))
      (node (ref "R5") (pin "1") (pinfunction "1_1") (pintype "passive"))
      (node (ref "R6") (pin "1") (pinfunction "1_1") (pintype "passive"))
      (node (ref "R9") (pin "1") (pinfunction "1_1") (pintype "passive"))
    )
    (net (code "9") (name "Net-(5VLED-PadC)") (class "Default")
      (node (ref "5VLED") (pin "C") (pinfunction "C_C") (pintype "passive"))
      (node (ref "R36") (pin "2") (pinfunction "2_2") (pintype "passive"))
    )
    (net (code "10") (name "Net-(13.75V-PadC)") (class "Default")
      (node (ref "13.75V") (pin "C") (pinfunction "C_C") (pintype "passive"))
      (node (ref "R34") (pin "2") (pinfunction "2_2") (pintype "passive"))
    )
    (net (code "11") (name "Net-(C17-Pad2)") (class "Default")
      (node (ref "C17") (pin "2") (pinfunction "2_2") (pintype "passive"))
      (node (ref "R15") (pin "2") (pinfunction "2_2") (pintype "passive"))
    )
    (net (code "12") (name "Net-(D5-K)") (class "Default")
      (node (ref "C27") (pin "1") (pinfunction "1_1") (pintype "passive"))
      (node (ref "D5") (pin "1") (pinfunction "K_1") (pintype "bidirectional"))
      (node (ref "IC4") (pin "6") (pinfunction "SW_6") (pintype "bidirectional"))
      (node (ref "L3") (pin "1") (pinfunction "1_1") (pintype "bidirectional"))
    )
    (net (code "13") (name "Net-(D6-K)") (class "Default")
      (node (ref "D6") (pin "1") (pinfunction "K_1") (pintype "bidirectional"))
      (node (ref "R16") (pin "1") (pinfunction "1_1") (pintype "passive"))
      (node (ref "R17") (pin "1") (pinfunction "1_1") (pintype "passive"))
    )
    (net (code "14") (name "Net-(D7-K)") (class "Default")
      (node (ref "C20") (pin "2") (pinfunction "2_2") (pintype "passive"))
      (node (ref "D7") (pin "1") (pinfunction "K_1") (pintype "bidirectional"))
      (node (ref "IC3") (pin "6") (pinfunction "SW_6") (pintype "bidirectional"))
      (node (ref "L2") (pin "2") (pinfunction "2_2") (pintype "bidirectional"))
    )
    (net (code "15") (name "Net-(D8-K)") (class "Default")
      (node (ref "D8") (pin "1") (pinfunction "K_1") (pintype "bidirectional"))
      (node (ref "D9") (pin "2") (pinfunction "A_2") (pintype "bidirectional"))
    )
    (net (code "16") (name "Net-(D9-K)") (class "Default")
      (node (ref "C32") (pin "2") (pinfunction "2_2") (pintype "passive"))
      (node (ref "D9") (pin "1") (pinfunction "K_1") (pintype "bidirectional"))
      (node (ref "PS1") (pin "3") (pinfunction "_+VIN_3") (pintype "bidirectional"))
    )
    (net (code "17") (name "Net-(D10-C)") (class "Default")
      (node (ref "C3") (pin "1") (pinfunction "1_1") (pintype "passive"))
      (node (ref "D10") (pin "1") (pinfunction "C_1") (pintype "passive"))
      (node (ref "R37") (pin "1") (pinfunction "1_1") (pintype "passive"))
    )
    (net (code "18") (name "Net-(D11-C)") (class "Default")
      (node (ref "C36") (pin "1") (pinfunction "1_1") (pintype "passive"))
      (node (ref "D11") (pin "1") (pinfunction "C_1") (pintype "passive"))
      (node (ref "R38") (pin "1") (pinfunction "1_1") (pintype "passive"))
    )
    (net (code "19") (name "Net-(HVLED-PadA)") (class "Default")
      (node (ref "HVLED") (pin "A") (pinfunction "A_A") (pintype "passive"))
      (node (ref "R30") (pin "1") (pinfunction "1_1") (pintype "passive"))
    )
    (net (code "20") (name "Net-(IC1-ENA)") (class "Default")
      (node (ref "IC1") (pin "1") (pinfunction "ENA_1") (pintype "bidirectional"))
      (node (ref "IC1") (pin "8") (pinfunction "ENB_8") (pintype "bidirectional"))
      (node (ref "R4") (pin "1") (pinfunction "1_1") (pintype "passive"))
    )
    (net (code "21") (name "Net-(IC1-INA)") (class "Default")
      (node (ref "IC1") (pin "2") (pinfunction "INA_2") (pintype "bidirectional"))
      (node (ref "IC2") (pin "7") (pinfunction "OUTA_7") (pintype "bidirectional"))
    )
    (net (code "22") (name "Net-(IC1-INB)") (class "Default")
      (node (ref "IC1") (pin "4") (pinfunction "INB_4") (pintype "bidirectional"))
      (node (ref "IC2") (pin "6") (pinfunction "OUTB_6") (pintype "bidirectional"))
    )
    (net (code "23") (name "Net-(IC1-OUT1)") (class "Default")
      (node (ref "IC1") (pin "7") (pinfunction "OUT1_7") (pintype "bidirectional"))
      (node (ref "R2") (pin "1") (pinfunction "1_1") (pintype "passive"))
      (node (ref "R3") (pin "1") (pinfunction "1_1") (pintype "passive"))
    )
    (net (code "24") (name "Net-(IC1-OUT2)") (class "Default")
      (node (ref "IC1") (pin "5") (pinfunction "OUT2_5") (pintype "bidirectional"))
      (node (ref "R7") (pin "1") (pinfunction "1_1") (pintype "passive"))
      (node (ref "R8") (pin "1") (pinfunction "1_1") (pintype "passive"))
    )
    (net (code "25") (name "Net-(IC2-CS)") (class "Default")
      (node (ref "C16") (pin "1") (pinfunction "1_1") (pintype "passive"))
      (node (ref "IC2") (pin "3") (pinfunction "CS_3") (pintype "bidirectional"))
      (node (ref "R11") (pin "1") (pinfunction "1_1") (pintype "passive"))
    )
    (net (code "26") (name "Net-(IC2-ISET)") (class "Default")
      (node (ref "IC2") (pin "2") (pinfunction "ISET_2") (pintype "bidirectional"))
      (node (ref "R13") (pin "1") (pinfunction "1_1") (pintype "passive"))
    )
    (net (code "27") (name "Net-(IC2-RT)") (class "Default")
      (node (ref "IC2") (pin "4") (pinfunction "RT_4") (pintype "bidirectional"))
      (node (ref "R14") (pin "1") (pinfunction "1_1") (pintype "passive"))
    )
    (net (code "28") (name "Net-(IC3-BS)") (class "Default")
      (node (ref "C20") (pin "1") (pinfunction "1_1") (pintype "passive"))
      (node (ref "IC3") (pin "1") (pinfunction "BS_1") (pintype "bidirectional"))
    )
    (net (code "29") (name "Net-(IC3-EN)") (class "Default")
      (node (ref "IC3") (pin "4") (pinfunction "EN_4") (pintype "bidirectional"))
      (node (ref "R20") (pin "2") (pinfunction "2_2") (pintype "passive"))
    )
    (net (code "30") (name "Net-(IC3-FB)") (class "Default")
      (node (ref "C19") (pin "2") (pinfunction "2_2") (pintype "passive"))
      (node (ref "IC3") (pin "3") (pinfunction "FB_3") (pintype "bidirectional"))
      (node (ref "R18") (pin "2") (pinfunction "2_2") (pintype "passive"))
      (node (ref "R19") (pin "1") (pinfunction "1_1") (pintype "passive"))
    )
    (net (code "31") (name "Net-(IC4-BS)") (class "Default")
      (node (ref "C27") (pin "2") (pinfunction "2_2") (pintype "passive"))
      (node (ref "IC4") (pin "1") (pinfunction "BS_1") (pintype "bidirectional"))
    )
    (net (code "32") (name "Net-(IC4-EN)") (class "Default")
      (node (ref "IC4") (pin "4") (pinfunction "EN_4") (pintype "bidirectional"))
      (node (ref "R33") (pin "2") (pinfunction "2_2") (pintype "passive"))
    )
    (net (code "33") (name "Net-(IC4-FB)") (class "Default")
      (node (ref "C25") (pin "2") (pinfunction "2_2") (pintype "passive"))
      (node (ref "IC4") (pin "3") (pinfunction "FB_3") (pintype "bidirectional"))
      (node (ref "R31") (pin "1") (pinfunction "1_1") (pintype "passive"))
      (node (ref "R32") (pin "1") (pinfunction "1_1") (pintype "passive"))
    )
    (net (code "34") (name "Net-(IC5-CATHODE)") (class "Default")
      (node (ref "C18") (pin "2") (pinfunction "2_2") (pintype "passive"))
      (node (ref "IC5") (pin "1") (pinfunction "CATHODE_1") (pintype "bidirectional"))
      (node (ref "OPT1") (pin "2") (pinfunction "K_2") (pintype "bidirectional"))
      (node (ref "R15") (pin "1") (pinfunction "1_1") (pintype "passive"))
    )
    (net (code "35") (name "Net-(IC5-REF)") (class "Default")
      (node (ref "C17") (pin "1") (pinfunction "1_1") (pintype "passive"))
      (node (ref "C18") (pin "1") (pinfunction "1_1") (pintype "passive"))
      (node (ref "IC5") (pin "2") (pinfunction "REF_2") (pintype "bidirectional"))
      (node (ref "J2") (pin "1") (pinfunction "1_1") (pintype "passive"))
      (node (ref "R22") (pin "2") (pinfunction "2_2") (pintype "passive"))
      (node (ref "R23") (pin "2") (pinfunction "2_2") (pintype "passive"))
    )
    (net (code "36") (name "Net-(OPT1-A)") (class "Default")
      (node (ref "OPT1") (pin "1") (pinfunction "A_1") (pintype "bidirectional"))
      (node (ref "R35") (pin "2") (pinfunction "2_2") (pintype "passive"))
    )
    (net (code "37") (name "Net-(Q1-G)") (class "Default")
      (node (ref "GATE1_TP") (pin "TP") (pinfunction "TP_TP") (pintype "input"))
      (node (ref "Q1") (pin "1") (pinfunction "G_1") (pintype "bidirectional"))
      (node (ref "R2") (pin "2") (pinfunction "2_2") (pintype "passive"))
      (node (ref "R3") (pin "2") (pinfunction "2_2") (pintype "passive"))
    )
    (net (code "38") (name "Net-(Q2-G)") (class "Default")
      (node (ref "GATE2_TP") (pin "TP") (pinfunction "TP_TP") (pintype "input"))
      (node (ref "Q2") (pin "1") (pinfunction "G_1") (pintype "bidirectional"))
      (node (ref "R7") (pin "2") (pinfunction "2_2") (pintype "passive"))
      (node (ref "R8") (pin "2") (pinfunction "2_2") (pintype "passive"))
    )
    (net (code "39") (name "Net-(R21-Pad2)") (class "Default")
      (node (ref "R21") (pin "2") (pinfunction "2_2") (pintype "passive"))
      (node (ref "R22") (pin "1") (pinfunction "1_1") (pintype "passive"))
    )
    (net (code "40") (name "Net-(R23-Pad1)") (class "Default")
      (node (ref "R23") (pin "1") (pinfunction "1_1") (pintype "passive"))
      (node (ref "R24") (pin "2") (pinfunction "2_2") (pintype "passive"))
    )
    (net (code "41") (name "Net-(R24-Pad1)") (class "Default")
      (node (ref "R24") (pin "1") (pinfunction "1_1") (pintype "passive"))
      (node (ref "R25") (pin "2") (pinfunction "2_2") (pintype "passive"))
    )
    (net (code "42") (name "Net-(R26-Pad1)") (class "Default")
      (node (ref "R26") (pin "1") (pinfunction "1_1") (pintype "passive"))
      (node (ref "R27") (pin "2") (pinfunction "2_2") (pintype "passive"))
    )
    (net (code "43") (name "Net-(R27-Pad1)") (class "Default")
      (node (ref "R27") (pin "1") (pinfunction "1_1") (pintype "passive"))
      (node (ref "R28") (pin "2") (pinfunction "2_2") (pintype "passive"))
    )
    (net (code "44") (name "Net-(R28-Pad1)") (class "Default")
      (node (ref "R28") (pin "1") (pinfunction "1_1") (pintype "passive"))
      (node (ref "R29") (pin "2") (pinfunction "2_2") (pintype "passive"))
    )
    (net (code "45") (name "Net-(R29-Pad1)") (class "Default")
      (node (ref "R29") (pin "1") (pinfunction "1_1") (pintype "passive"))
      (node (ref "R30") (pin "2") (pinfunction "2_2") (pintype "passive"))
    )
    (net (code "46") (name "Net-(SJ100-Pad1)") (class "Default")
      (node (ref "SJ100") (pin "1") (pinfunction "1_1") (pintype "passive"))
      (node (ref "T1") (pin "11") (pinfunction "11_11") (pintype "bidirectional"))
    )
    (net (code "47") (name "Net-(SJ100-Pad3)") (class "Default")
      (node (ref "SJ100") (pin "3") (pinfunction "3_3") (pintype "passive"))
      (node (ref "T1") (pin "13") (pinfunction "13_13") (pintype "bidirectional"))
    )
    (net (code "48") (name "Net-(VR1-ADJ)") (class "Default")
      (node (ref "R10") (pin "1") (pinfunction "1_1") (pintype "passive"))
      (node (ref "R9") (pin "2") (pinfunction "2_2") (pintype "passive"))
      (node (ref "VR1") (pin "1") (pinfunction "ADJ_1") (pintype "input"))
    )
    (net (code "49") (name "OPTO-EMITT") (class "Default")
      (node (ref "IC2") (pin "1") (pinfunction "CTRL_1") (pintype "bidirectional"))
      (node (ref "OPT1") (pin "4") (pinfunction "C_4") (pintype "bidirectional"))
      (node (ref "R12") (pin "2") (pinfunction "2_2") (pintype "passive"))
    )
    (net (code "50") (name "PRE") (class "Default")
      (node (ref "C25") (pin "1") (pinfunction "1_1") (pintype "passive"))
      (node (ref "C28") (pin "2") (pinfunction "2_2") (pintype "passive"))
      (node (ref "C29") (pin "2") (pinfunction "2_2") (pintype "passive"))
      (node (ref "C30") (pin "2") (pinfunction "2_2") (pintype "passive"))
      (node (ref "L3") (pin "2") (pinfunction "2_2") (pintype "bidirectional"))
      (node (ref "MAINBUCK_TP") (pin "TP") (pinfunction "TP_TP") (pintype "input"))
      (node (ref "R32") (pin "2") (pinfunction "2_2") (pintype "passive"))
      (node (ref "VR1") (pin "3") (pinfunction "IN_3") (pintype "input"))
    )
    (net (code "51") (name "PWRGND") (class "Default")
      (node (ref "C21") (pin "2") (pinfunction "2_2") (pintype "passive"))
      (node (ref "C22") (pin "1") (pinfunction "1_1") (pintype "passive"))
      (node (ref "C23") (pin "1") (pinfunction "1_1") (pintype "passive"))
      (node (ref "C24") (pin "1") (pinfunction "1_1") (pintype "passive"))
      (node (ref "C33") (pin "1") (pinfunction "1_1") (pintype "passive"))
      (node (ref "C34") (pin "2") (pinfunction "2_2") (pintype "passive"))
      (node (ref "C35") (pin "1") (pinfunction "1_1") (pintype "passive"))
      (node (ref "C4") (pin "2") (pinfunction "2_2") (pintype "bidirectional"))
      (node (ref "C5") (pin "2") (pinfunction "2_2") (pintype "bidirectional"))
      (node (ref "C6") (pin "2") (pinfunction "-_2") (pintype "bidirectional"))
      (node (ref "C7") (pin "2") (pinfunction "-_2") (pintype "bidirectional"))
      (node (ref "D1") (pin "1") (pinfunction "A1_1") (pintype "bidirectional"))
      (node (ref "D1") (pin "3") (pinfunction "A2_3") (pintype "bidirectional"))
      (node (ref "D3") (pin "1") (pinfunction "A1_1") (pintype "bidirectional"))
      (node (ref "D3") (pin "3") (pinfunction "A2_3") (pintype "bidirectional"))
      (node (ref "D7") (pin "2") (pinfunction "A_2") (pintype "bidirectional"))
      (node (ref "HVLED") (pin "C") (pinfunction "C_C") (pintype "passive"))
      (node (ref "IC3") (pin "2") (pinfunction "GND_2") (pintype "bidirectional"))
      (node (ref "IC5") (pin "3") (pinfunction "ANODE_3") (pintype "bidirectional"))
      (node (ref "J1") (pin "1") (pinfunction "1_1") (pintype "bidirectional"))
      (node (ref "J2") (pin "2") (pinfunction "2_2") (pintype "passive"))
      (node (ref "PS1") (pin "7") (pinfunction "-VOUT_7") (pintype "bidirectional"))
      (node (ref "PWRGND_TP") (pin "TP") (pinfunction "TP_TP") (pintype "input"))
      (node (ref "R19") (pin "2") (pinfunction "2_2") (pintype "passive"))
      (node (ref "R21") (pin "1") (pinfunction "1_1") (pintype "passive"))
      (node (ref "R36") (pin "1") (pinfunction "1_1") (pintype "passive"))
      (node (ref "T1") (pin "15") (pinfunction "15_15") (pintype "bidirectional"))
      (node (ref "T1.1") (pin "4") (pinfunction "4_4") (pintype "bidirectional"))
      (node (ref "VR2") (pin "1") (pinfunction "GND_1") (pintype "bidirectional"))
      (node (ref "Z3") (pin "2") (pinfunction "A_2") (pintype "bidirectional"))
    )
    (net (code "52") (name "RECT") (class "Default")
      (node (ref "D2") (pin "2") (pinfunction "K_2") (pintype "bidirectional"))
      (node (ref "D4") (pin "2") (pinfunction "K_2") (pintype "bidirectional"))
      (node (ref "L1") (pin "1") (pinfunction "1_1") (pintype "bidirectional"))
    )
    (net (code "53") (name "REG") (class "Default")
      (node (ref "13.75V") (pin "A") (pinfunction "A_A") (pintype "passive"))
      (node (ref "13.75V_TP") (pin "TP") (pinfunction "TP_TP") (pintype "input"))
      (node (ref "C10") (pin "2") (pinfunction "2_2") (pintype "passive"))
      (node (ref "C14") (pin "1") (pinfunction "1_1") (pintype "passive"))
      (node (ref "C15") (pin "1") (pinfunction "1_1") (pintype "passive"))
      (node (ref "C31") (pin "2") (pinfunction "2_2") (pintype "passive"))
      (node (ref "C9") (pin "1") (pinfunction "1_1") (pintype "passive"))
      (node (ref "D8") (pin "2") (pinfunction "A_2") (pintype "bidirectional"))
      (node (ref "IC1") (pin "6") (pinfunction "VDD_6") (pintype "bidirectional"))
      (node (ref "IC2") (pin "8") (pinfunction "VDD_8") (pintype "bidirectional"))
      (node (ref "R10") (pin "2") (pinfunction "2_2") (pintype "passive"))
      (node (ref "R12") (pin "1") (pinfunction "1_1") (pintype "passive"))
      (node (ref "R4") (pin "2") (pinfunction "2_2") (pintype "passive"))
      (node (ref "VR1") (pin "4") (pinfunction "OUT_4") (pintype "passive"))
    )
    (net (code "54") (name "REG5V") (class "Default")
      (node (ref "5VLED") (pin "A") (pinfunction "A_A") (pintype "passive"))
      (node (ref "AUX5V_TP") (pin "TP") (pinfunction "TP_TP") (pintype "input"))
      (node (ref "C33") (pin "2") (pinfunction "2_2") (pintype "passive"))
      (node (ref "C35") (pin "2") (pinfunction "2_2") (pintype "passive"))
      (node (ref "PS1") (pin "8") (pinfunction "+VOUT_8") (pintype "bidirectional"))
      (node (ref "R35") (pin "1") (pinfunction "1_1") (pintype "passive"))
      (node (ref "VR2") (pin "2") (pinfunction "VOUT_2") (pintype "bidirectional"))
    )
    (net (code "55") (name "TRANS1") (class "Default")
      (node (ref "D1") (pin "2") (pinfunction "K_2") (pintype "bidirectional"))
      (node (ref "D2") (pin "1") (pinfunction "A1_1") (pintype "bidirectional"))
      (node (ref "D2") (pin "3") (pinfunction "A2_3") (pintype "bidirectional"))
      (node (ref "SJ100") (pin "2") (pinfunction "2_2") (pintype "passive"))
      (node (ref "T1.1") (pin "8") (pinfunction "8_8") (pintype "bidirectional"))
    )
    (net (code "56") (name "TRANS2") (class "Default")
      (node (ref "D3") (pin "2") (pinfunction "K_2") (pintype "bidirectional"))
      (node (ref "D4") (pin "1") (pinfunction "A1_1") (pintype "bidirectional"))
      (node (ref "D4") (pin "3") (pinfunction "A2_3") (pintype "bidirectional"))
      (node (ref "T1") (pin "9") (pinfunction "9_9") (pintype "bidirectional"))
      (node (ref "T1.1") (pin "14") (pinfunction "14_14") (pintype "bidirectional"))
    )
    (net (code "57") (name "VCC28V") (class "Default")
      (node (ref "C1") (pin "1") (pinfunction "+_1") (pintype "bidirectional"))
      (node (ref "C11") (pin "2") (pinfunction "2_2") (pintype "passive"))
      (node (ref "C12") (pin "1") (pinfunction "+_1") (pintype "bidirectional"))
      (node (ref "C13") (pin "1") (pinfunction "+_1") (pintype "bidirectional"))
      (node (ref "C2") (pin "1") (pinfunction "+_1") (pintype "bidirectional"))
      (node (ref "C26") (pin "1") (pinfunction "1_1") (pintype "passive"))
      (node (ref "C3") (pin "2") (pinfunction "2_2") (pintype "passive"))
      (node (ref "C36") (pin "2") (pinfunction "2_2") (pintype "passive"))
      (node (ref "C8") (pin "1") (pinfunction "1_1") (pintype "passive"))
      (node (ref "IC4") (pin "5") (pinfunction "IN_5") (pintype "bidirectional"))
      (node (ref "INPUT") (pin "1") (pinfunction "1_1") (pintype "bidirectional"))
      (node (ref "R33") (pin "1") (pinfunction "1_1") (pintype "passive"))
      (node (ref "R37") (pin "2") (pinfunction "2_2") (pintype "passive"))
      (node (ref "R38") (pin "2") (pinfunction "2_2") (pintype "passive"))
      (node (ref "T1") (pin "4") (pinfunction "4_4") (pintype "bidirectional"))
      (node (ref "T1") (pin "5") (pinfunction "5_5") (pintype "bidirectional"))
      (node (ref "T1.1") (pin "7") (pinfunction "7_7") (pintype "bidirectional"))
    )
    (net (code "58") (name "unconnected-(PS1-NA-Pad14)") (class "Default")
      (node (ref "PS1") (pin "14") (pinfunction "NA_14") (pintype "bidirectional"))
    )
    (net (code "59") (name "unconnected-(T1-Pad10)") (class "Default")
      (node (ref "T1") (pin "10") (pinfunction "10_10") (pintype "bidirectional"))
    )
    (net (code "60") (name "unconnected-(T1-Pad12)") (class "Default")
      (node (ref "T1") (pin "12") (pinfunction "12_12") (pintype "bidirectional"))
    )
    (net (code "61") (name "unconnected-(T1-Pad14)") (class "Default")
      (node (ref "T1") (pin "14") (pinfunction "14_14") (pintype "bidirectional"))
    )
    (net (code "62") (name "unconnected-(T1.1-Pad6)") (class "Default")
      (node (ref "T1.1") (pin "6") (pinfunction "6_6") (pintype "bidirectional"))
    )
    (net (code "63") (name "unconnected-(T1.1-Pad10)") (class "Default")
      (node (ref "T1.1") (pin "10") (pinfunction "10_10") (pintype "bidirectional"))
    )
    (net (code "64") (name "unconnected-(T1.1-Pad12)") (class "Default")
      (node (ref "T1.1") (pin "12") (pinfunction "12_12") (pintype "bidirectional"))
    )
  )
)
